# diode_sampling_gate.net
KiCad netlist of a schematic drawn in EAGLE
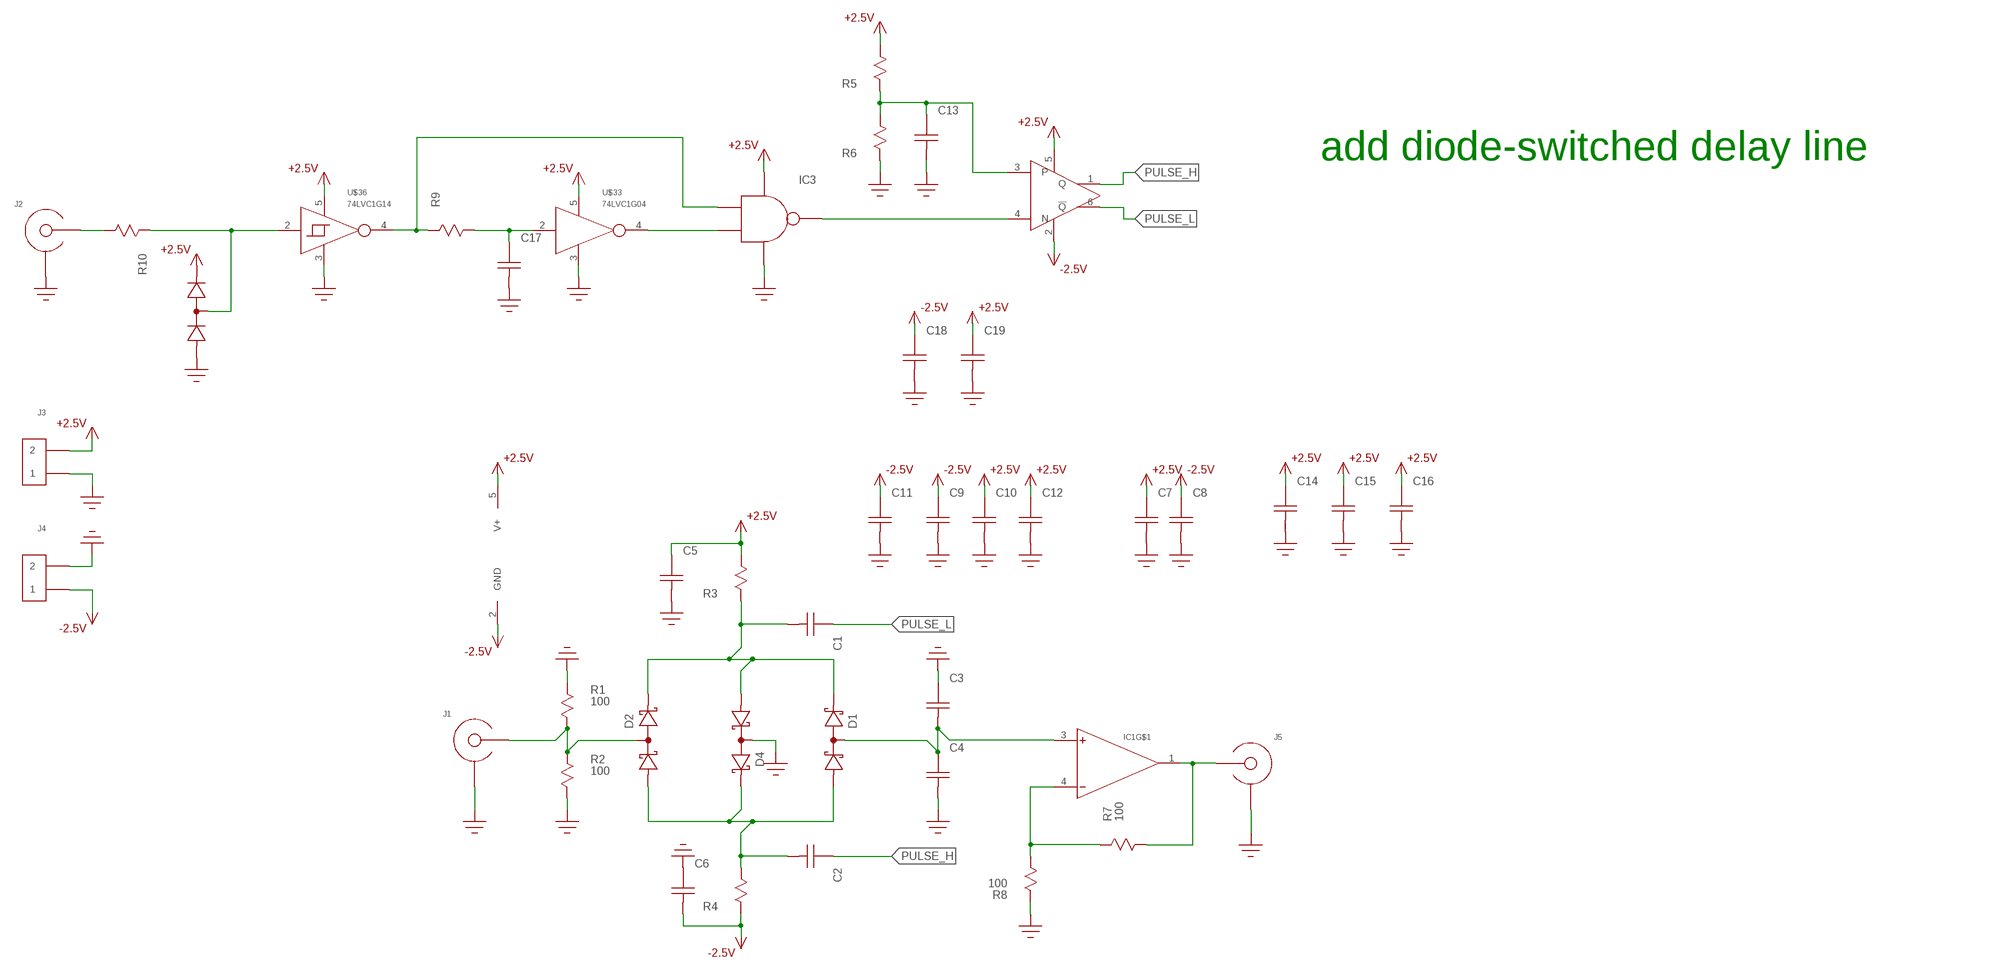
[diagram p0: schematic, sheet 1]

(export (version "E")
  (design (tool "Eeschema 10.0.6"))
  (components
    (comp (ref "C1")
      (value "C0603")
      (footprint "eagle-import:C0603")
      (libsource (lib "eagle-import") (part "C0603"))
    )
    (comp (ref "C2")
      (value "C0603")
      (footprint "eagle-import:C0603")
      (libsource (lib "eagle-import") (part "C0603"))
    )
    (comp (ref "C3")
      (value "C0603")
      (footprint "eagle-import:C0603")
      (libsource (lib "eagle-import") (part "C0603"))
    )
    (comp (ref "C4")
      (value "C0603")
      (footprint "eagle-import:C0603")
      (libsource (lib "eagle-import") (part "C0603"))
    )
    (comp (ref "C5")
      (value "C0603")
      (footprint "eagle-import:C0603")
      (libsource (lib "eagle-import") (part "C0603"))
    )
    (comp (ref "C6")
      (value "C0603")
      (footprint "eagle-import:C0603")
      (libsource (lib "eagle-import") (part "C0603"))
    )
    (comp (ref "C7") (value "C") (footprint "eagle-import:C0402") (libsource (lib "eagle-import") (part "C")))
    (comp (ref "C8") (value "C") (footprint "eagle-import:C0402") (libsource (lib "eagle-import") (part "C")))
    (comp (ref "C9")
      (value "C0603")
      (footprint "eagle-import:C0603")
      (libsource (lib "eagle-import") (part "C0603"))
    )
    (comp (ref "C10")
      (value "C0603")
      (footprint "eagle-import:C0603")
      (libsource (lib "eagle-import") (part "C0603"))
    )
    (comp (ref "C11")
      (value "C0805")
      (footprint "eagle-import:0805")
      (libsource (lib "eagle-import") (part "C0805"))
    )
    (comp (ref "C12")
      (value "C0805")
      (footprint "eagle-import:0805")
      (libsource (lib "eagle-import") (part "C0805"))
    )
    (comp (ref "C13")
      (value "C0603")
      (footprint "eagle-import:C0603")
      (libsource (lib "eagle-import") (part "C0603"))
    )
    (comp (ref "C14")
      (value "C0603")
      (footprint "eagle-import:C0603")
      (libsource (lib "eagle-import") (part "C0603"))
    )
    (comp (ref "C15")
      (value "C0603")
      (footprint "eagle-import:C0603")
      (libsource (lib "eagle-import") (part "C0603"))
    )
    (comp (ref "C16")
      (value "C0603")
      (footprint "eagle-import:C0603")
      (libsource (lib "eagle-import") (part "C0603"))
    )
    (comp (ref "C17")
      (value "C0603")
      (footprint "eagle-import:C0603")
      (libsource (lib "eagle-import") (part "C0603"))
    )
    (comp (ref "C18")
      (value "C0805")
      (footprint "eagle-import:0805")
      (libsource (lib "eagle-import") (part "C0805"))
    )
    (comp (ref "C19")
      (value "C0805")
      (footprint "eagle-import:0805")
      (libsource (lib "eagle-import") (part "C0805"))
    )
    (comp (ref "D1")
      (value "BAS40-04")
      (footprint "eagle-import:SOT-23")
      (libsource (lib "eagle-import") (part "BAS40-04"))
    )
    (comp (ref "D2")
      (value "BAS40-04")
      (footprint "eagle-import:SOT-23")
      (libsource (lib "eagle-import") (part "BAS40-04"))
    )
    (comp (ref "D4")
      (value "BAS40-04")
      (footprint "eagle-import:SOT-23")
      (libsource (lib "eagle-import") (part "BAS40-04"))
    )
    (comp (ref "IC1")
      (value "MCP6V81")
      (footprint "eagle-import:SOT23-5")
      (libsource (lib "eagle-import") (part "MCP6V81"))
    )
    (comp (ref "IC2")
      (value "ADCMP606")
      (footprint "eagle-import:SC70-6")
      (libsource (lib "eagle-import") (part "ADCMP606"))
    )
    (comp (ref "IC3")
      (value "74LVC1G00")
      (footprint "eagle-import:SOT23-5")
      (libsource (lib "eagle-import") (part "74LVC1G00"))
    )
    (comp (ref "J1")
      (value "EDGE_LAUNCH_JACK")
      (footprint "eagle-import:EDGE_LAUNCH_RF_CON")
      (libsource (lib "eagle-import") (part "EDGE_LAUNCH_JACK"))
    )
    (comp (ref "J2")
      (value "EDGE_LAUNCH_JACK")
      (footprint "eagle-import:EDGE_LAUNCH_RF_CON")
      (libsource (lib "eagle-import") (part "EDGE_LAUNCH_JACK"))
    )
    (comp (ref "J3")
      (value "HEADER_2PIN")
      (footprint "eagle-import:HEADER_2PIN")
      (libsource (lib "eagle-import") (part "HEADER_2PIN"))
    )
    (comp (ref "J4")
      (value "HEADER_2PIN")
      (footprint "eagle-import:HEADER_2PIN")
      (libsource (lib "eagle-import") (part "HEADER_2PIN"))
    )
    (comp (ref "J5")
      (value "EDGE_LAUNCH_JACK")
      (footprint "eagle-import:EDGE_LAUNCH_RF_CON")
      (libsource (lib "eagle-import") (part "EDGE_LAUNCH_JACK"))
    )
    (comp (ref "R1")
      (value "100")
      (footprint "eagle-import:R0603")
      (libsource (lib "eagle-import") (part "R0603"))
    )
    (comp (ref "R2")
      (value "100")
      (footprint "eagle-import:R0603")
      (libsource (lib "eagle-import") (part "R0603"))
    )
    (comp (ref "R3")
      (value "R0603")
      (footprint "eagle-import:R0603")
      (libsource (lib "eagle-import") (part "R0603"))
    )
    (comp (ref "R4")
      (value "R0603")
      (footprint "eagle-import:R0603")
      (libsource (lib "eagle-import") (part "R0603"))
    )
    (comp (ref "R5")
      (value "R0603")
      (footprint "eagle-import:R0603")
      (libsource (lib "eagle-import") (part "R0603"))
    )
    (comp (ref "R6")
      (value "R0603")
      (footprint "eagle-import:R0603")
      (libsource (lib "eagle-import") (part "R0603"))
    )
    (comp (ref "R7")
      (value "100")
      (footprint "eagle-import:R0603")
      (libsource (lib "eagle-import") (part "R0603"))
    )
    (comp (ref "R8")
      (value "100")
      (footprint "eagle-import:R0603")
      (libsource (lib "eagle-import") (part "R0603"))
    )
    (comp (ref "R9")
      (value "R0603")
      (footprint "eagle-import:R0603")
      (libsource (lib "eagle-import") (part "R0603"))
    )
    (comp (ref "R10")
      (value "R0603")
      (footprint "eagle-import:R0603")
      (libsource (lib "eagle-import") (part "R0603"))
    )
    (comp (ref "U$33")
      (value "74LVC1G04")
      (footprint "eagle-import:SOT23-5")
      (libsource (lib "eagle-import") (part "74LVC1G04"))
    )
    (comp (ref "U$36")
      (value "74LVC1G14")
      (footprint "eagle-import:SOT23-5")
      (libsource (lib "eagle-import") (part "74LVC1G14"))
    )
    (comp (ref "U$46")
      (value "MMBD7000L")
      (footprint "eagle-import:SOT-23")
      (libsource (lib "eagle-import") (part "MMBD7000L"))
    )
  )
  (nets
    (net (code "1") (name "+2.5V") (class "Default")
      (node (ref "C10") (pin "P$2") (pinfunction "P$2_P$2") (pintype "bidirectional"))
      (node (ref "C12") (pin "P$2") (pinfunction "P$2_P$2") (pintype "bidirectional"))
      (node (ref "C14") (pin "P$2") (pinfunction "P$2_P$2") (pintype "bidirectional"))
      (node (ref "C15") (pin "P$2") (pinfunction "P$2_P$2") (pintype "bidirectional"))
      (node (ref "C16") (pin "P$2") (pinfunction "P$2_P$2") (pintype "bidirectional"))
      (node (ref "C19") (pin "P$2") (pinfunction "P$2_P$2") (pintype "bidirectional"))
      (node (ref "C5") (pin "P$2") (pinfunction "P$2_P$2") (pintype "bidirectional"))
      (node (ref "C7") (pin "2") (pinfunction "P$2_2") (pintype "bidirectional"))
      (node (ref "IC1") (pin "5") (pinfunction "V+_5") (pintype "bidirectional"))
      (node (ref "IC2") (pin "5") (pinfunction "VCC_5") (pintype "bidirectional"))
      (node (ref "IC3") (pin "5") (pinfunction "VCC_5") (pintype "bidirectional"))
      (node (ref "J3") (pin "2") (pinfunction "2_2") (pintype "bidirectional"))
      (node (ref "R3") (pin "P$2") (pinfunction "P$4_P$2") (pintype "bidirectional"))
      (node (ref "R5") (pin "P$2") (pinfunction "P$4_P$2") (pintype "bidirectional"))
      (node (ref "U$33") (pin "5") (pinfunction "VCC_5") (pintype "bidirectional"))
      (node (ref "U$36") (pin "5") (pinfunction "VCC_5") (pintype "bidirectional"))
      (node (ref "U$46") (pin "2") (pinfunction "CATHODE_2") (pintype "bidirectional"))
    )
    (net (code "2") (name "-2.5V") (class "Default")
      (node (ref "C11") (pin "P$2") (pinfunction "P$2_P$2") (pintype "bidirectional"))
      (node (ref "C18") (pin "P$2") (pinfunction "P$2_P$2") (pintype "bidirectional"))
      (node (ref "C6") (pin "P$1") (pinfunction "P$1_P$1") (pintype "bidirectional"))
      (node (ref "C8") (pin "2") (pinfunction "P$2_2") (pintype "bidirectional"))
      (node (ref "C9") (pin "P$2") (pinfunction "P$2_P$2") (pintype "bidirectional"))
      (node (ref "IC1") (pin "2") (pinfunction "GND_2") (pintype "bidirectional"))
      (node (ref "IC2") (pin "2") (pinfunction "VEE_2") (pintype "bidirectional"))
      (node (ref "J4") (pin "1") (pinfunction "1_1") (pintype "bidirectional"))
      (node (ref "R4") (pin "P$1") (pinfunction "P$3_P$1") (pintype "bidirectional"))
    )
    (net (code "3") (name "GND") (class "Default")
      (node (ref "C10") (pin "P$1") (pinfunction "P$1_P$1") (pintype "bidirectional"))
      (node (ref "C11") (pin "P$1") (pinfunction "P$1_P$1") (pintype "bidirectional"))
      (node (ref "C12") (pin "P$1") (pinfunction "P$1_P$1") (pintype "bidirectional"))
      (node (ref "C13") (pin "P$1") (pinfunction "P$1_P$1") (pintype "bidirectional"))
      (node (ref "C14") (pin "P$1") (pinfunction "P$1_P$1") (pintype "bidirectional"))
      (node (ref "C15") (pin "P$1") (pinfunction "P$1_P$1") (pintype "bidirectional"))
      (node (ref "C16") (pin "P$1") (pinfunction "P$1_P$1") (pintype "bidirectional"))
      (node (ref "C17") (pin "P$1") (pinfunction "P$1_P$1") (pintype "bidirectional"))
      (node (ref "C18") (pin "P$1") (pinfunction "P$1_P$1") (pintype "bidirectional"))
      (node (ref "C19") (pin "P$1") (pinfunction "P$1_P$1") (pintype "bidirectional"))
      (node (ref "C3") (pin "P$2") (pinfunction "P$2_P$2") (pintype "bidirectional"))
      (node (ref "C4") (pin "P$1") (pinfunction "P$1_P$1") (pintype "bidirectional"))
      (node (ref "C5") (pin "P$1") (pinfunction "P$1_P$1") (pintype "bidirectional"))
      (node (ref "C6") (pin "P$2") (pinfunction "P$2_P$2") (pintype "bidirectional"))
      (node (ref "C7") (pin "1") (pinfunction "P$1_1") (pintype "bidirectional"))
      (node (ref "C8") (pin "1") (pinfunction "P$1_1") (pintype "bidirectional"))
      (node (ref "C9") (pin "P$1") (pinfunction "P$1_P$1") (pintype "bidirectional"))
      (node (ref "D4") (pin "3") (pinfunction "COMMON_3") (pintype "bidirectional"))
      (node (ref "IC3") (pin "3") (pinfunction "GND_3") (pintype "bidirectional"))
      (node (ref "J1") (pin "GND@1") (pinfunction "SHIELD_GND@1") (pintype "bidirectional"))
      (node (ref "J1") (pin "GND@10") (pinfunction "SHIELD_GND@10") (pintype "bidirectional"))
      (node (ref "J1") (pin "GND@11") (pinfunction "SHIELD_GND@11") (pintype "bidirectional"))
      (node (ref "J1") (pin "GND@12") (pinfunction "SHIELD_GND@12") (pintype "bidirectional"))
      (node (ref "J1") (pin "GND@2") (pinfunction "SHIELD_GND@2") (pintype "bidirectional"))
      (node (ref "J1") (pin "GND@3") (pinfunction "SHIELD_GND@3") (pintype "bidirectional"))
      (node (ref "J1") (pin "GND@4") (pinfunction "SHIELD_GND@4") (pintype "bidirectional"))
      (node (ref "J1") (pin "GND@5") (pinfunction "SHIELD_GND@5") (pintype "bidirectional"))
      (node (ref "J1") (pin "GND@6") (pinfunction "SHIELD_GND@6") (pintype "bidirectional"))
      (node (ref "J1") (pin "GND@7") (pinfunction "SHIELD_GND@7") (pintype "bidirectional"))
      (node (ref "J1") (pin "GND@8") (pinfunction "SHIELD_GND@8") (pintype "bidirectional"))
      (node (ref "J1") (pin "GND@9") (pinfunction "SHIELD_GND@9") (pintype "bidirectional"))
      (node (ref "J1") (pin "SHIELD@1") (pinfunction "SHIELD_SHIELD@1") (pintype "bidirectional"))
      (node (ref "J1") (pin "SHIELD@2") (pinfunction "SHIELD_SHIELD@2") (pintype "bidirectional"))
      (node (ref "J2") (pin "GND@1") (pinfunction "SHIELD_GND@1") (pintype "bidirectional"))
      (node (ref "J2") (pin "GND@10") (pinfunction "SHIELD_GND@10") (pintype "bidirectional"))
      (node (ref "J2") (pin "GND@11") (pinfunction "SHIELD_GND@11") (pintype "bidirectional"))
      (node (ref "J2") (pin "GND@12") (pinfunction "SHIELD_GND@12") (pintype "bidirectional"))
      (node (ref "J2") (pin "GND@2") (pinfunction "SHIELD_GND@2") (pintype "bidirectional"))
      (node (ref "J2") (pin "GND@3") (pinfunction "SHIELD_GND@3") (pintype "bidirectional"))
      (node (ref "J2") (pin "GND@4") (pinfunction "SHIELD_GND@4") (pintype "bidirectional"))
      (node (ref "J2") (pin "GND@5") (pinfunction "SHIELD_GND@5") (pintype "bidirectional"))
      (node (ref "J2") (pin "GND@6") (pinfunction "SHIELD_GND@6") (pintype "bidirectional"))
      (node (ref "J2") (pin "GND@7") (pinfunction "SHIELD_GND@7") (pintype "bidirectional"))
      (node (ref "J2") (pin "GND@8") (pinfunction "SHIELD_GND@8") (pintype "bidirectional"))
      (node (ref "J2") (pin "GND@9") (pinfunction "SHIELD_GND@9") (pintype "bidirectional"))
      (node (ref "J2") (pin "SHIELD@1") (pinfunction "SHIELD_SHIELD@1") (pintype "bidirectional"))
      (node (ref "J2") (pin "SHIELD@2") (pinfunction "SHIELD_SHIELD@2") (pintype "bidirectional"))
      (node (ref "J3") (pin "1") (pinfunction "1_1") (pintype "bidirectional"))
      (node (ref "J4") (pin "2") (pinfunction "2_2") (pintype "bidirectional"))
      (node (ref "J5") (pin "GND@1") (pinfunction "SHIELD_GND@1") (pintype "bidirectional"))
      (node (ref "J5") (pin "GND@10") (pinfunction "SHIELD_GND@10") (pintype "bidirectional"))
      (node (ref "J5") (pin "GND@11") (pinfunction "SHIELD_GND@11") (pintype "bidirectional"))
      (node (ref "J5") (pin "GND@12") (pinfunction "SHIELD_GND@12") (pintype "bidirectional"))
      (node (ref "J5") (pin "GND@2") (pinfunction "SHIELD_GND@2") (pintype "bidirectional"))
      (node (ref "J5") (pin "GND@3") (pinfunction "SHIELD_GND@3") (pintype "bidirectional"))
      (node (ref "J5") (pin "GND@4") (pinfunction "SHIELD_GND@4") (pintype "bidirectional"))
      (node (ref "J5") (pin "GND@5") (pinfunction "SHIELD_GND@5") (pintype "bidirectional"))
      (node (ref "J5") (pin "GND@6") (pinfunction "SHIELD_GND@6") (pintype "bidirectional"))
      (node (ref "J5") (pin "GND@7") (pinfunction "SHIELD_GND@7") (pintype "bidirectional"))
      (node (ref "J5") (pin "GND@8") (pinfunction "SHIELD_GND@8") (pintype "bidirectional"))
      (node (ref "J5") (pin "GND@9") (pinfunction "SHIELD_GND@9") (pintype "bidirectional"))
      (node (ref "J5") (pin "SHIELD@1") (pinfunction "SHIELD_SHIELD@1") (pintype "bidirectional"))
      (node (ref "J5") (pin "SHIELD@2") (pinfunction "SHIELD_SHIELD@2") (pintype "bidirectional"))
      (node (ref "R1") (pin "P$1") (pinfunction "P$3_P$1") (pintype "bidirectional"))
      (node (ref "R2") (pin "P$2") (pinfunction "P$4_P$2") (pintype "bidirectional"))
      (node (ref "R6") (pin "P$1") (pinfunction "P$3_P$1") (pintype "bidirectional"))
      (node (ref "R8") (pin "P$1") (pinfunction "P$3_P$1") (pintype "bidirectional"))
      (node (ref "U$33") (pin "3") (pinfunction "GND_3") (pintype "bidirectional"))
      (node (ref "U$36") (pin "3") (pinfunction "GND_3") (pintype "bidirectional"))
      (node (ref "U$46") (pin "1") (pinfunction "ANODE_1") (pintype "bidirectional"))
    )
    (net (code "4") (name "Net-(D1-ANODE)") (class "Default")
      (node (ref "C2") (pin "P$1") (pinfunction "P$1_P$1") (pintype "bidirectional"))
      (node (ref "D1") (pin "1") (pinfunction "ANODE_1") (pintype "bidirectional"))
      (node (ref "D2") (pin "1") (pinfunction "ANODE_1") (pintype "bidirectional"))
      (node (ref "D4") (pin "2") (pinfunction "CATHODE_2") (pintype "bidirectional"))
      (node (ref "R4") (pin "P$2") (pinfunction "P$4_P$2") (pintype "bidirectional"))
    )
    (net (code "5") (name "Net-(D1-CATHODE)") (class "Default")
      (node (ref "C1") (pin "P$1") (pinfunction "P$1_P$1") (pintype "bidirectional"))
      (node (ref "D1") (pin "2") (pinfunction "CATHODE_2") (pintype "bidirectional"))
      (node (ref "D2") (pin "2") (pinfunction "CATHODE_2") (pintype "bidirectional"))
      (node (ref "D4") (pin "1") (pinfunction "ANODE_1") (pintype "bidirectional"))
      (node (ref "R3") (pin "P$1") (pinfunction "P$3_P$1") (pintype "bidirectional"))
    )
    (net (code "6") (name "Net-(D1-COMMON)") (class "Default")
      (node (ref "C3") (pin "P$1") (pinfunction "P$1_P$1") (pintype "bidirectional"))
      (node (ref "C4") (pin "P$2") (pinfunction "P$2_P$2") (pintype "bidirectional"))
      (node (ref "D1") (pin "3") (pinfunction "COMMON_3") (pintype "bidirectional"))
      (node (ref "IC1") (pin "3") (pinfunction "+_3") (pintype "bidirectional"))
    )
    (net (code "7") (name "Net-(D2-COMMON)") (class "Default")
      (node (ref "D2") (pin "3") (pinfunction "COMMON_3") (pintype "bidirectional"))
      (node (ref "J1") (pin "CENTER") (pinfunction "CENTER_CENTER") (pintype "bidirectional"))
      (node (ref "R1") (pin "P$2") (pinfunction "P$4_P$2") (pintype "bidirectional"))
      (node (ref "R2") (pin "P$1") (pinfunction "P$3_P$1") (pintype "bidirectional"))
    )
    (net (code "8") (name "Net-(IC1A--)") (class "Default")
      (node (ref "IC1") (pin "4") (pinfunction "-_4") (pintype "bidirectional"))
      (node (ref "R7") (pin "P$1") (pinfunction "P$3_P$1") (pintype "bidirectional"))
      (node (ref "R8") (pin "P$2") (pinfunction "P$4_P$2") (pintype "bidirectional"))
    )
    (net (code "9") (name "Net-(IC1A-OUT)") (class "Default")
      (node (ref "IC1") (pin "1") (pinfunction "OUT_1") (pintype "bidirectional"))
      (node (ref "J5") (pin "CENTER") (pinfunction "CENTER_CENTER") (pintype "bidirectional"))
      (node (ref "R7") (pin "P$2") (pinfunction "P$4_P$2") (pintype "bidirectional"))
    )
    (net (code "10") (name "Net-(IC2-N)") (class "Default")
      (node (ref "IC2") (pin "4") (pinfunction "N_4") (pintype "bidirectional"))
      (node (ref "IC3") (pin "4") (pinfunction "Y_4") (pintype "bidirectional"))
    )
    (net (code "11") (name "Net-(IC2-P)") (class "Default")
      (node (ref "C13") (pin "P$2") (pinfunction "P$2_P$2") (pintype "bidirectional"))
      (node (ref "IC2") (pin "3") (pinfunction "P_3") (pintype "bidirectional"))
      (node (ref "R5") (pin "P$1") (pinfunction "P$3_P$1") (pintype "bidirectional"))
      (node (ref "R6") (pin "P$2") (pinfunction "P$4_P$2") (pintype "bidirectional"))
    )
    (net (code "12") (name "Net-(IC3-A)") (class "Default")
      (node (ref "IC3") (pin "2") (pinfunction "A_2") (pintype "bidirectional"))
      (node (ref "R9") (pin "P$1") (pinfunction "P$3_P$1") (pintype "bidirectional"))
      (node (ref "U$36") (pin "4") (pinfunction "OUT_4") (pintype "bidirectional"))
    )
    (net (code "13") (name "Net-(IC3-B)") (class "Default")
      (node (ref "IC3") (pin "1") (pinfunction "B_1") (pintype "bidirectional"))
      (node (ref "U$33") (pin "4") (pinfunction "OUT_4") (pintype "bidirectional"))
    )
    (net (code "14") (name "Net-(R9-P$4)") (class "Default")
      (node (ref "C17") (pin "P$2") (pinfunction "P$2_P$2") (pintype "bidirectional"))
      (node (ref "R9") (pin "P$2") (pinfunction "P$4_P$2") (pintype "bidirectional"))
      (node (ref "U$33") (pin "2") (pinfunction "IN_2") (pintype "bidirectional"))
    )
    (net (code "15") (name "Net-(R10-P$3)") (class "Default")
      (node (ref "R10") (pin "P$1") (pinfunction "P$3_P$1") (pintype "bidirectional"))
      (node (ref "U$36") (pin "2") (pinfunction "IN_2") (pintype "bidirectional"))
      (node (ref "U$46") (pin "3") (pinfunction "COMMON_3") (pintype "bidirectional"))
    )
    (net (code "16") (name "Net-(R10-P$4)") (class "Default")
      (node (ref "J2") (pin "CENTER") (pinfunction "CENTER_CENTER") (pintype "bidirectional"))
      (node (ref "R10") (pin "P$2") (pinfunction "P$4_P$2") (pintype "bidirectional"))
    )
    (net (code "17") (name "PULSE_H") (class "Default")
      (node (ref "C2") (pin "P$2") (pinfunction "P$2_P$2") (pintype "bidirectional"))
      (node (ref "IC2") (pin "1") (pinfunction "Q_1") (pintype "bidirectional"))
    )
    (net (code "18") (name "PULSE_L") (class "Default")
      (node (ref "C1") (pin "P$2") (pinfunction "P$2_P$2") (pintype "bidirectional"))
      (node (ref "IC2") (pin "6") (pinfunction "~{Q}_6") (pintype "bidirectional"))
    )
  )
)
